# MCUPower.net
KiCad netlist of a schematic drawn in Altium Designer
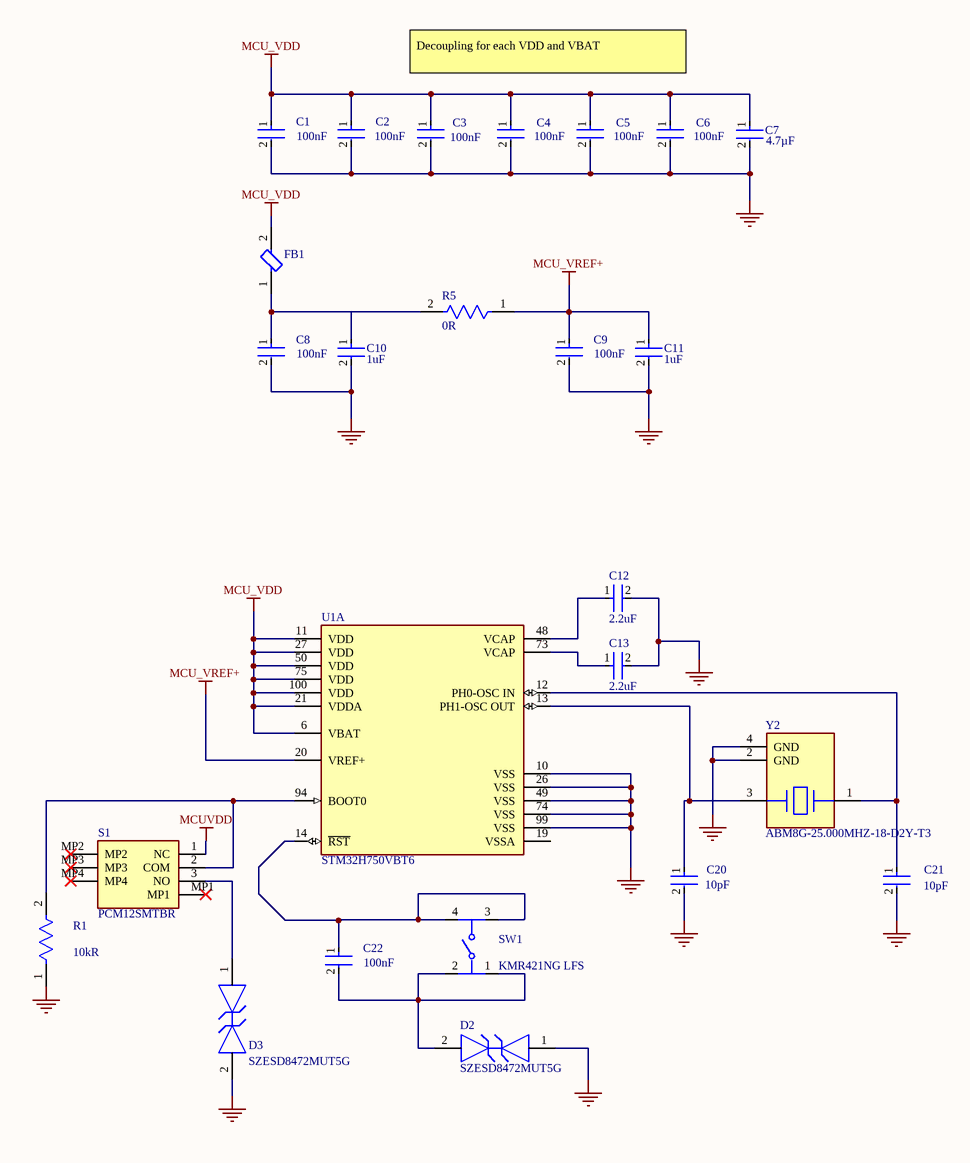
[diagram p0: MCUPower.SchDoc]

(export (version "E")
  (design (tool "Eeschema 10.0.6"))
  (components
    (comp (ref "C1")
      (value "GCM155R71H104ME02J")
      (footprint "FP-GCM155-0_05-IPC_A")
      (description "Ceramic Capacitor for Automotive 100nF ±20% 50VDC X7R 0402 Paper T/R")
      (fields (field (name "CAPACITANCE") "100nF"))
      (libsource (lib "Altium Content Vault") (part "02cd4be3c70576c341d710602a673aa"))
    )
    (comp (ref "C2")
      (value "GCM155R71H104ME02J")
      (footprint "FP-GCM155-0_05-IPC_A")
      (description "Ceramic Capacitor for Automotive 100nF ±20% 50VDC X7R 0402 Paper T/R")
      (fields (field (name "CAPACITANCE") "100nF"))
      (libsource (lib "Altium Content Vault") (part "02cd4be3c70576c341d710602a673aa"))
    )
    (comp (ref "C3")
      (value "GCM155R71H104ME02J")
      (footprint "FP-GCM155-0_05-IPC_A")
      (description "Ceramic Capacitor for Automotive 100nF ±20% 50VDC X7R 0402 Paper T/R")
      (fields (field (name "CAPACITANCE") "100nF"))
      (libsource (lib "Altium Content Vault") (part "02cd4be3c70576c341d710602a673aa"))
    )
    (comp (ref "C4")
      (value "GCM155R71H104ME02J")
      (footprint "FP-GCM155-0_05-IPC_A")
      (description "Ceramic Capacitor for Automotive 100nF ±20% 50VDC X7R 0402 Paper T/R")
      (fields (field (name "CAPACITANCE") "100nF"))
      (libsource (lib "Altium Content Vault") (part "02cd4be3c70576c341d710602a673aa"))
    )
    (comp (ref "C5")
      (value "GCM155R71H104ME02J")
      (footprint "FP-GCM155-0_05-IPC_A")
      (description "Ceramic Capacitor for Automotive 100nF ±20% 50VDC X7R 0402 Paper T/R")
      (fields (field (name "CAPACITANCE") "100nF"))
      (libsource (lib "Altium Content Vault") (part "02cd4be3c70576c341d710602a673aa"))
    )
    (comp (ref "C6")
      (value "GCM155R71H104ME02J")
      (footprint "FP-GCM155-0_05-IPC_A")
      (description "Ceramic Capacitor for Automotive 100nF ±20% 50VDC X7R 0402 Paper T/R")
      (fields (field (name "CAPACITANCE") "100nF"))
      (libsource (lib "Altium Content Vault") (part "02cd4be3c70576c341d710602a673aa"))
    )
    (comp (ref "C7")
      (value "GCM155M8EB475ME08D")
      (footprint "FP-GCM155-0_2-MFG")
      (description "GCM155M8EB475ME08D Chip MultilayerCeramicCapacitors")
      (fields (field (name "TOLERANCE") "20%") (field (name "CAPACITANCE") "4.7µF"))
      (libsource (lib "Altium Content Vault") (part "b4654b650e69147ec39a6b967a45e02"))
    )
    (comp (ref "C8")
      (value "GCM155R71H104ME02J")
      (footprint "FP-GCM155-0_05-IPC_A")
      (description "Ceramic Capacitor for Automotive 100nF ±20% 50VDC X7R 0402 Paper T/R")
      (fields (field (name "CAPACITANCE") "100nF"))
      (libsource (lib "Altium Content Vault") (part "02cd4be3c70576c341d710602a673aa"))
    )
    (comp (ref "C9")
      (value "GCM155R71H104ME02J")
      (footprint "FP-GCM155-0_05-IPC_A")
      (description "Ceramic Capacitor for Automotive 100nF ±20% 50VDC X7R 0402 Paper T/R")
      (fields (field (name "CAPACITANCE") "100nF"))
      (libsource (lib "Altium Content Vault") (part "02cd4be3c70576c341d710602a673aa"))
    )
    (comp (ref "C10")
      (value "GCM155C71A105KE38D")
      (footprint "FP-GCM155-0_2-MFG")
      (description "CAP CER 1UF 10V X7S 0402")
      (fields (field (name "CAPACITANCE") "1uF") (field (name "TOLERANCE") "10%"))
      (libsource (lib "Altium Content Vault") (part "11868f565c42a9108669ba33697ecf6"))
    )
    (comp (ref "C11")
      (value "GCM155C71A105KE38D")
      (footprint "FP-GCM155-0_2-MFG")
      (description "CAP CER 1UF 10V X7S 0402")
      (fields (field (name "CAPACITANCE") "1uF") (field (name "TOLERANCE") "10%"))
      (libsource (lib "Altium Content Vault") (part "11868f565c42a9108669ba33697ecf6"))
    )
    (comp (ref "C12")
      (value "GCM188C71A225KE02D")
      (footprint "FP-GCH188-0_1-e0_2_0_5-MFG")
      (description "GCM188C71A225KE02D Multilayer Ceramic Capacitor, 2.2 uF, 10 V, ± 10%, X7S, 0603 [1608 Metric]")
      (fields (field (name "CAPACITANCE") "2.2uF"))
      (libsource (lib "Altium Content Vault") (part "b4654b650e69147ec39a6b967a45e02"))
    )
    (comp (ref "C13")
      (value "GCM188C71A225KE02D")
      (footprint "FP-GCH188-0_1-e0_2_0_5-MFG")
      (description "GCM188C71A225KE02D Multilayer Ceramic Capacitor, 2.2 uF, 10 V, ± 10%, X7S, 0603 [1608 Metric]")
      (fields (field (name "CAPACITANCE") "2.2uF"))
      (libsource (lib "Altium Content Vault") (part "b4654b650e69147ec39a6b967a45e02"))
    )
    (comp (ref "C20")
      (value "GCM1555G1H100GA16D")
      (footprint "FP-GCM155-0_05-IPC_B")
      (description "Ceramic Capacitor for Automotive 10pF ±2% 50VDC X8G 0402 Paper T/R")
      (fields (field (name "CAPACITANCE") "10pF"))
      (libsource (lib "Altium Content Vault") (part "02cd4be3c70576c341d710602a673aa"))
    )
    (comp (ref "C21")
      (value "GCM1555G1H100GA16D")
      (footprint "FP-GCM155-0_05-IPC_B")
      (description "Ceramic Capacitor for Automotive 10pF ±2% 50VDC X8G 0402 Paper T/R")
      (fields (field (name "CAPACITANCE") "10pF"))
      (libsource (lib "Altium Content Vault") (part "02cd4be3c70576c341d710602a673aa"))
    )
    (comp (ref "C22")
      (value "GCM155R71H104ME02J")
      (footprint "FP-GCM155-0_05-IPC_A")
      (description "Ceramic Capacitor for Automotive 100nF ±20% 50VDC X7R 0402 Paper T/R")
      (fields (field (name "CAPACITANCE") "100nF"))
      (libsource (lib "Altium Content Vault") (part "02cd4be3c70576c341d710602a673aa"))
    )
    (comp (ref "D2")
      (value "SZESD8472MUT5G")
      (footprint "FP-152AF-MFG")
      (description "TVS DIODE 5.3V 14V 2X3DFN")
      (libsource (lib "Altium Content Vault") (part "9a4650ba5e636bd8b2e4c4fb393e9aa"))
    )
    (comp (ref "D3")
      (value "SZESD8472MUT5G")
      (footprint "FP-152AF-MFG")
      (description "TVS DIODE 5.3V 14V 2X3DFN")
      (libsource (lib "Altium Content Vault") (part "9a4650ba5e636bd8b2e4c4fb393e9aa"))
    )
    (comp (ref "FB1")
      (value "BLM15BX102SZ1D")
      (footprint "FP-BLM15-0_05-MFG")
      (description "Chip Ferrite Bead, 0402, 1000Ω @ 100MHz, 0.65Ω, 25%, 300mA")
      (libsource (lib "Altium Content Vault") (part "5f30dd21d616792df468990f7003faa"))
    )
    (comp (ref "R1")
      (value "RC0402FR-1310KL")
      (footprint "FP-RC0402-0_4-IPC_A")
      (description "RESISTOR 0402 10K 1%")
      (fields (field (name "RESISTANCE") "10kR") (field (name "TOLERANCE") "1%"))
      (libsource (lib "Altium Content Vault") (part "1029c3af85768c4190bb7ad29bc67b5"))
    )
    (comp (ref "R5")
      (value "RMCF0402ZT0R00")
      (footprint "FP-RMCF0402-MFG")
      (description "RES 0 OHM JUMPER 1/16W 0402")
      (fields (field (name "RESISTANCE") "0R"))
      (libsource (lib "Altium Content Vault") (part "1029c3af85768c4190bb7ad29bc67b5"))
    )
    (comp (ref "S1")
      (value "PCM12SMTBR")
      (footprint "SamacSys:PCM12SMTBR")
      (description "Switch")
      (fields (field (name "MOUSER PART NUMBER") "611-PCM12SMTBR"))
      (libsource (lib "*") (part "PCM12SMTBR"))
    )
    (comp (ref "SW1")
      (value "KMR421NG LFS")
      (footprint "FP-KMR421NG_LFS-MFG")
      (description "SWITCH TACTILE SPST-NO 0.05A 32V")
      (fields
        (field (name "MANUFACTURER") "C&K Components")
        (field (name "OCTOPART") "https://octopart.com/kmr421nglfs-c%26k+components-7226706")
      )
      (libsource (lib "Altium Content Vault") (part "82b636f13fd696edb7519609c0a8a76"))
    )
    (comp (ref "U1")
      (value "STM32H750VBT6")
      (footprint "FP-LQFP100-1L-MFG")
      (description "IC MCU 32BIT 128KB FLASH 100LQFP")
      (fields
        (field (name "OCTOPART") "https://octopart.com/stm32h750vbt6-stmicroelectronics-94048547")
        (field (name "MANUFACTURER") "STMicroelectronics")
      )
      (libsource (lib "Altium Content Vault") (part "aca449acb2b80670ba40d015d68dc7a"))
    )
    (comp (ref "Y2")
      (value "ABM8G-25.000MHZ-18-D2Y-T3")
      (footprint "FP-ABM8G-MFG")
      (description "Crystal 25MHz ±20ppm (Tol) ±30ppm (Stability) 18pF FUND 60Ω 4-Pin SMD T/R")
      (fields (field (name "TOLERANCE") "20ppm"))
      (libsource (lib "Altium Content Vault") (part "48e526d86b7f2615d98721063c72f49"))
    )
  )
  (nets
    (net (code "1") (name "GND") (class "Default")
      (node (ref "C1") (pin "2") (pinfunction "2_2") (pintype "passive"))
      (node (ref "C10") (pin "2") (pinfunction "2_2") (pintype "passive"))
      (node (ref "C11") (pin "2") (pinfunction "2_2") (pintype "passive"))
      (node (ref "C12") (pin "2") (pinfunction "2_2") (pintype "passive"))
      (node (ref "C13") (pin "2") (pinfunction "2_2") (pintype "passive"))
      (node (ref "C2") (pin "2") (pinfunction "2_2") (pintype "passive"))
      (node (ref "C20") (pin "2") (pinfunction "2_2") (pintype "passive"))
      (node (ref "C21") (pin "2") (pinfunction "2_2") (pintype "passive"))
      (node (ref "C3") (pin "2") (pinfunction "2_2") (pintype "passive"))
      (node (ref "C4") (pin "2") (pinfunction "2_2") (pintype "passive"))
      (node (ref "C5") (pin "2") (pinfunction "2_2") (pintype "passive"))
      (node (ref "C6") (pin "2") (pinfunction "2_2") (pintype "passive"))
      (node (ref "C7") (pin "2") (pinfunction "2_2") (pintype "passive"))
      (node (ref "C8") (pin "2") (pinfunction "2_2") (pintype "passive"))
      (node (ref "C9") (pin "2") (pinfunction "2_2") (pintype "passive"))
      (node (ref "D2") (pin "1") (pinfunction "1_1") (pintype "passive"))
      (node (ref "D3") (pin "2") (pinfunction "2_2") (pintype "passive"))
      (node (ref "R1") (pin "1") (pinfunction "1_1") (pintype "passive"))
      (node (ref "U1") (pin "10") (pinfunction "VSS_10") (pintype "power_in"))
      (node (ref "U1") (pin "26") (pinfunction "VSS_26") (pintype "power_in"))
      (node (ref "U1") (pin "49") (pinfunction "VSS_49") (pintype "power_in"))
      (node (ref "U1") (pin "74") (pinfunction "VSS_74") (pintype "power_in"))
      (node (ref "U1") (pin "99") (pinfunction "VSS_99") (pintype "power_in"))
      (node (ref "Y2") (pin "2") (pinfunction "GND_2") (pintype "power_in"))
      (node (ref "Y2") (pin "4") (pinfunction "GND_4") (pintype "power_in"))
    )
    (net (code "2") (name "MCUVDD") (class "Default")
      (node (ref "S1") (pin "1") (pinfunction "NC_1") (pintype "passive"))
    )
    (net (code "3") (name "MCU_VDD") (class "Default")
      (node (ref "C1") (pin "1") (pinfunction "1_1") (pintype "passive"))
      (node (ref "C2") (pin "1") (pinfunction "1_1") (pintype "passive"))
      (node (ref "C3") (pin "1") (pinfunction "1_1") (pintype "passive"))
      (node (ref "C4") (pin "1") (pinfunction "1_1") (pintype "passive"))
      (node (ref "C5") (pin "1") (pinfunction "1_1") (pintype "passive"))
      (node (ref "C6") (pin "1") (pinfunction "1_1") (pintype "passive"))
      (node (ref "C7") (pin "1") (pinfunction "1_1") (pintype "passive"))
      (node (ref "FB1") (pin "2") (pinfunction "2_2") (pintype "passive"))
      (node (ref "U1") (pin "100") (pinfunction "VDD_100") (pintype "power_in"))
      (node (ref "U1") (pin "11") (pinfunction "VDD_11") (pintype "power_in"))
      (node (ref "U1") (pin "21") (pinfunction "VDDA_21") (pintype "power_in"))
      (node (ref "U1") (pin "27") (pinfunction "VDD_27") (pintype "power_in"))
      (node (ref "U1") (pin "50") (pinfunction "VDD_50") (pintype "power_in"))
      (node (ref "U1") (pin "6") (pinfunction "VBAT_6") (pintype "power_in"))
      (node (ref "U1") (pin "75") (pinfunction "VDD_75") (pintype "power_in"))
    )
    (net (code "4") (name "MCU_VREF+") (class "Default")
      (node (ref "C11") (pin "1") (pinfunction "1_1") (pintype "passive"))
      (node (ref "C9") (pin "1") (pinfunction "1_1") (pintype "passive"))
      (node (ref "R5") (pin "1") (pinfunction "1_1") (pintype "passive"))
      (node (ref "U1") (pin "20") (pinfunction "VREF+_20") (pintype "power_in"))
    )
    (net (code "5") (name "Net-(C10-Pad1)") (class "Default")
      (node (ref "C10") (pin "1") (pinfunction "1_1") (pintype "passive"))
      (node (ref "C8") (pin "1") (pinfunction "1_1") (pintype "passive"))
      (node (ref "FB1") (pin "1") (pinfunction "1_1") (pintype "passive"))
      (node (ref "R5") (pin "2") (pinfunction "2_2") (pintype "passive"))
    )
    (net (code "6") (name "Net-(C12-Pad1)") (class "Default")
      (node (ref "C12") (pin "1") (pinfunction "1_1") (pintype "passive"))
      (node (ref "U1") (pin "48") (pinfunction "VCAP_48") (pintype "power_in"))
    )
    (net (code "7") (name "Net-(C13-Pad1)") (class "Default")
      (node (ref "C13") (pin "1") (pinfunction "1_1") (pintype "passive"))
      (node (ref "U1") (pin "73") (pinfunction "VCAP_73") (pintype "power_in"))
    )
    (net (code "8") (name "Net-(C22-Pad2)") (class "Default")
      (node (ref "C22") (pin "2") (pinfunction "2_2") (pintype "passive"))
      (node (ref "D2") (pin "2") (pinfunction "2_2") (pintype "passive"))
      (node (ref "SW1") (pin "1") (pinfunction "1_1") (pintype "passive"))
      (node (ref "SW1") (pin "2") (pinfunction "2_2") (pintype "passive"))
    )
    (net (code "9") (name "Net-(S1-COM)") (class "Default")
      (node (ref "R1") (pin "2") (pinfunction "2_2") (pintype "passive"))
      (node (ref "S1") (pin "2") (pinfunction "COM_2") (pintype "passive"))
      (node (ref "U1") (pin "94") (pinfunction "BOOT0_94") (pintype "input"))
    )
    (net (code "10") (name "Net-(S1-NO)") (class "Default")
      (node (ref "D3") (pin "1") (pinfunction "1_1") (pintype "passive"))
      (node (ref "S1") (pin "3") (pinfunction "NO_3") (pintype "passive"))
    )
    (net (code "11") (name "Net-(U1A-PH0-OSC_IN)") (class "Default")
      (node (ref "C21") (pin "1") (pinfunction "1_1") (pintype "passive"))
      (node (ref "U1") (pin "12") (pinfunction "PH0-OSC_IN_12") (pintype "bidirectional"))
      (node (ref "Y2") (pin "1") (pinfunction "1_1") (pintype "passive"))
    )
    (net (code "12") (name "Net-(U1A-PH1-OSC_OUT)") (class "Default")
      (node (ref "C20") (pin "1") (pinfunction "1_1") (pintype "passive"))
      (node (ref "U1") (pin "13") (pinfunction "PH1-OSC_OUT_13") (pintype "bidirectional"))
      (node (ref "Y2") (pin "3") (pinfunction "3_3") (pintype "passive"))
    )
    (net (code "13") (name "Net-(U1A-~{RST})") (class "Default")
      (node (ref "C22") (pin "1") (pinfunction "1_1") (pintype "passive"))
      (node (ref "SW1") (pin "3") (pinfunction "3_3") (pintype "passive"))
      (node (ref "SW1") (pin "4") (pinfunction "4_4") (pintype "passive"))
      (node (ref "U1") (pin "14") (pinfunction "~{RST}_14") (pintype "bidirectional"))
    )
    (net (code "14") (name "unconnected-(S1-PadMP1)") (class "Default")
      (node (ref "S1") (pin "MP1") (pinfunction "MP1_MP1") (pintype "passive+no_connect"))
    )
    (net (code "15") (name "unconnected-(S1-PadMP2)") (class "Default")
      (node (ref "S1") (pin "MP2") (pinfunction "MP2_MP2") (pintype "passive+no_connect"))
    )
    (net (code "16") (name "unconnected-(S1-PadMP3)") (class "Default")
      (node (ref "S1") (pin "MP3") (pinfunction "MP3_MP3") (pintype "passive+no_connect"))
    )
    (net (code "17") (name "unconnected-(S1-PadMP4)") (class "Default")
      (node (ref "S1") (pin "MP4") (pinfunction "MP4_MP4") (pintype "passive+no_connect"))
    )
    (net (code "18") (name "unconnected-(U1A-VSSA-Pad19)") (class "Default")
      (node (ref "U1") (pin "19") (pinfunction "VSSA_19") (pintype "power_in"))
    )
  )
)
